# SkyRover.net
KiCad netlist of a schematic drawn in Altium Designer
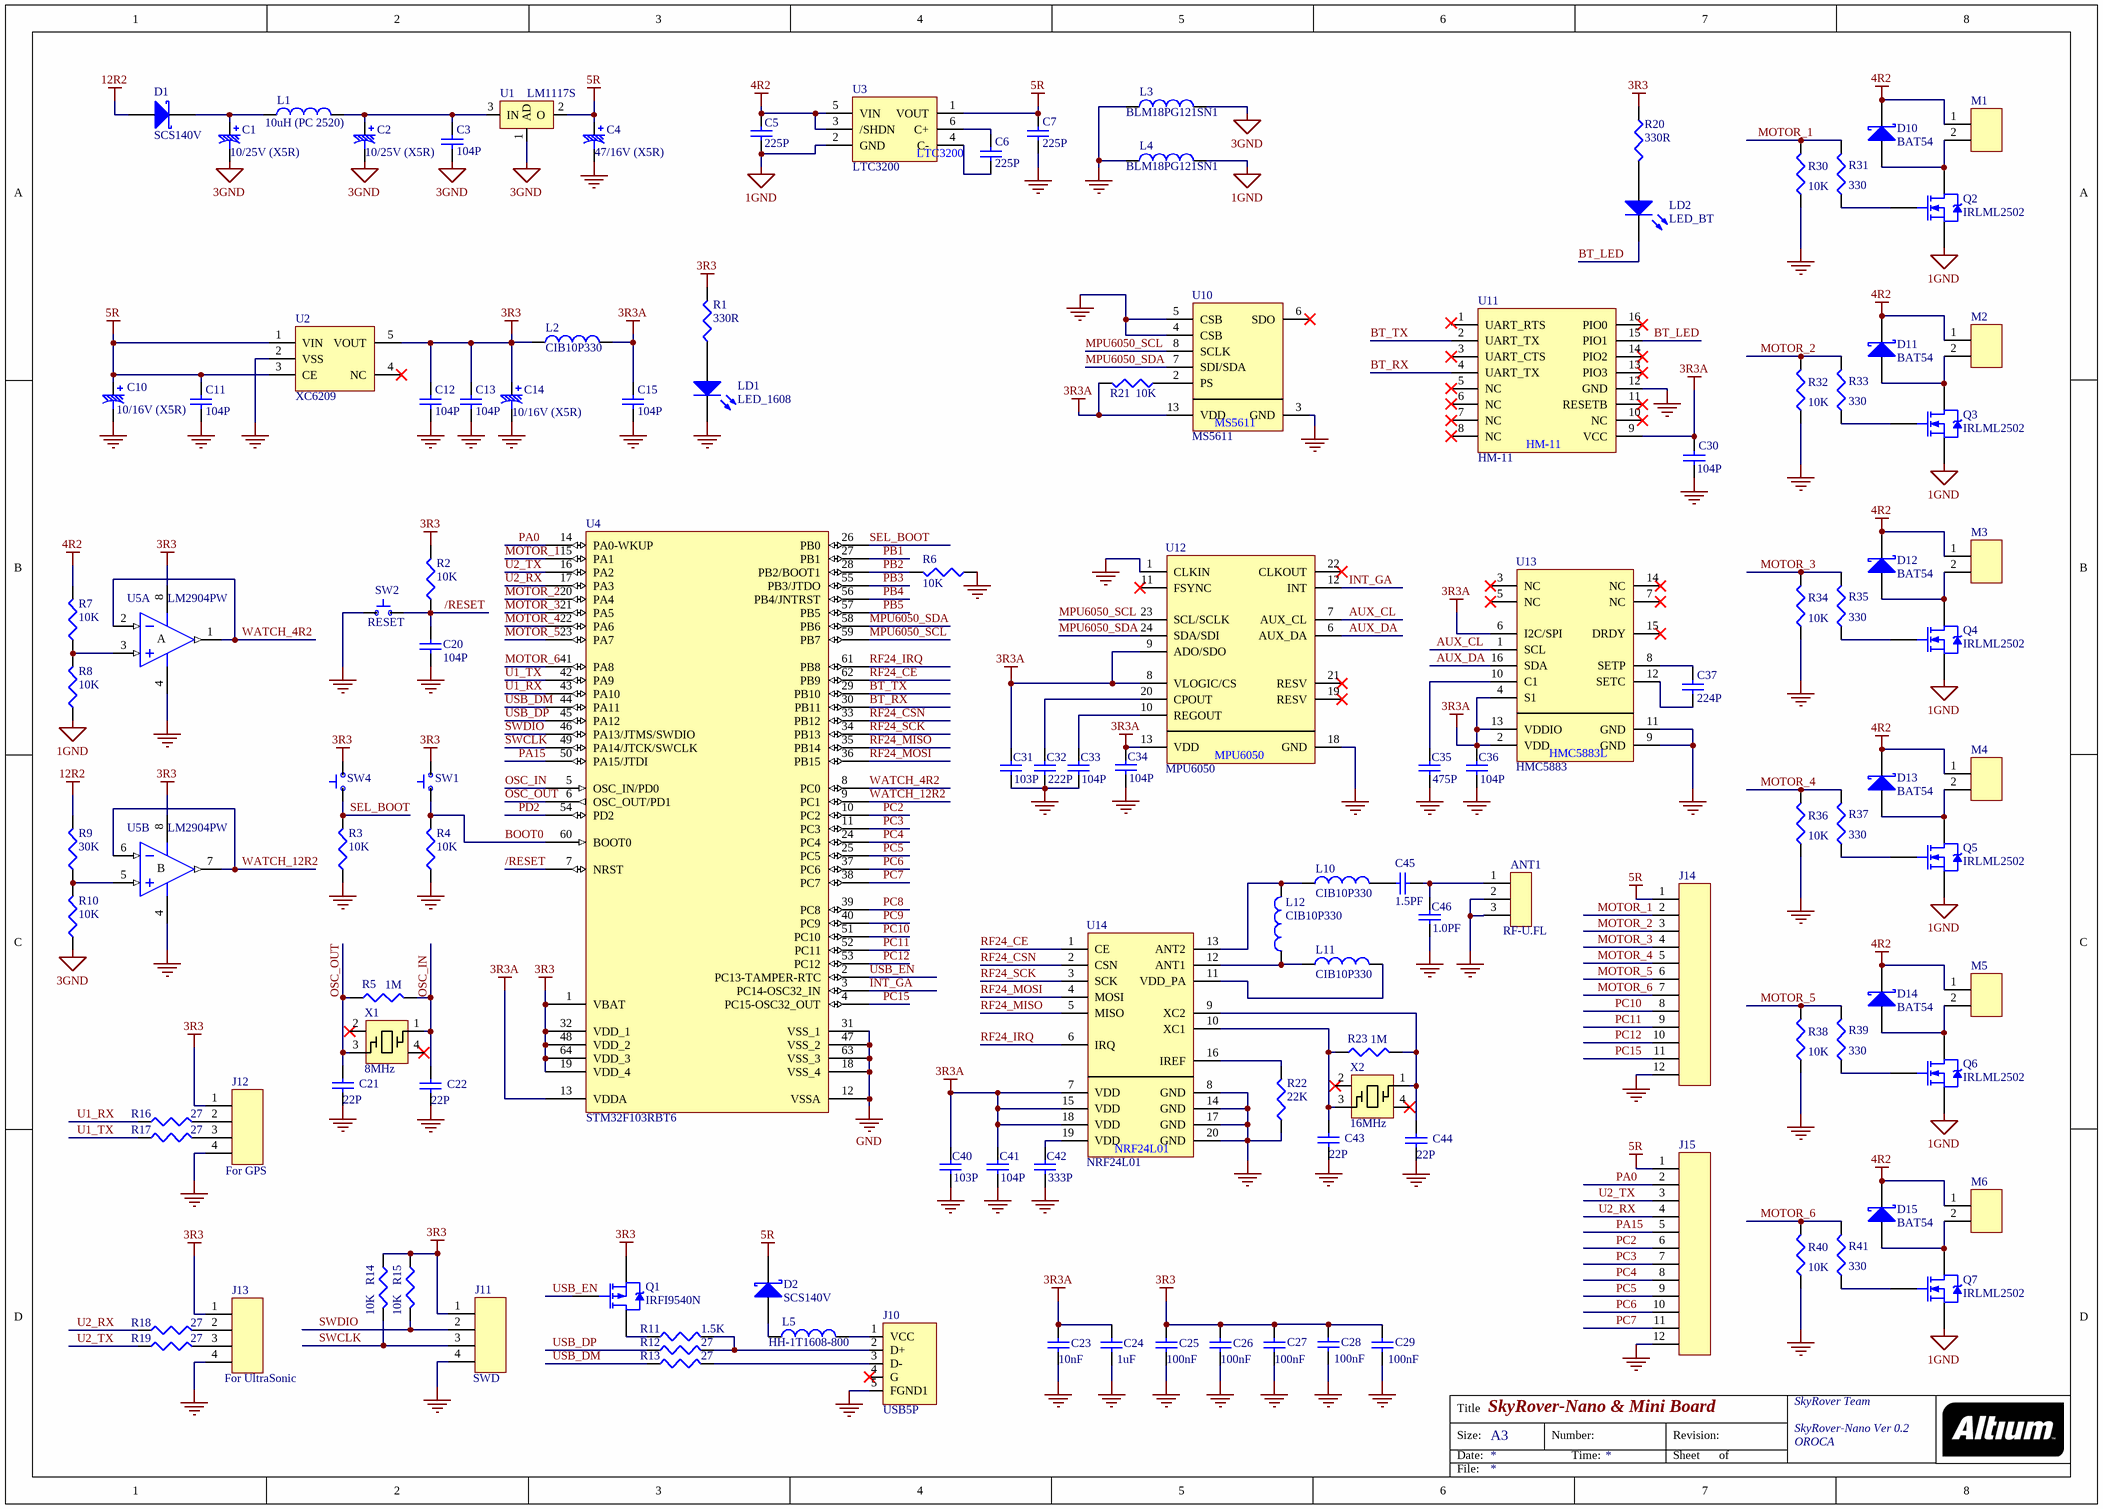
[diagram p0: SkyRover.SchDoc]

(export (version "E")
  (design (tool "Eeschema 10.0.6"))
  (components
    (comp (ref "ANT1") (value "RF-U.FL") (footprint "U.FL-R-SMT") (libsource (lib "KDG1") (part "RF-U.FL")))
    (comp (ref "C1")
      (value "10/25V (X5R)")
      (footprint "C_3.2X1.6")
      (description "Electrolytic Capacitor")
      (libsource (lib "烹钦扼捞宏矾府") (part "CAP_ELEC"))
    )
    (comp (ref "C2")
      (value "10/25V (X5R)")
      (footprint "C_3.2X1.6")
      (description "Electrolytic Capacitor")
      (libsource (lib "烹钦扼捞宏矾府") (part "CAP_ELEC"))
    )
    (comp (ref "C3")
      (value "104P")
      (footprint "C_1608(0603)")
      (description "Ceramic Capacitor")
      (libsource (lib "烹钦扼捞宏矾府") (part "CAP"))
    )
    (comp (ref "C4")
      (value "47/16V (X5R)")
      (footprint "C_3.2X1.6")
      (description "Electrolytic Capacitor")
      (libsource (lib "烹钦扼捞宏矾府") (part "CAP_ELEC"))
    )
    (comp (ref "C5")
      (value "225P")
      (footprint "C_1608(0603)")
      (description "Ceramic Capacitor")
      (libsource (lib "烹钦扼捞宏矾府") (part "CAP"))
    )
    (comp (ref "C6")
      (value "225P")
      (footprint "C_1608(0603)")
      (description "Ceramic Capacitor")
      (libsource (lib "烹钦扼捞宏矾府") (part "CAP"))
    )
    (comp (ref "C7")
      (value "225P")
      (footprint "C_1608(0603)")
      (description "Ceramic Capacitor")
      (libsource (lib "烹钦扼捞宏矾府") (part "CAP"))
    )
    (comp (ref "C10")
      (value "10/16V (X5R)")
      (footprint "C_3.2X1.6")
      (description "Electrolytic Capacitor")
      (libsource (lib "烹钦扼捞宏矾府") (part "CAP_ELEC"))
    )
    (comp (ref "C11")
      (value "104P")
      (footprint "C_1608(0603)")
      (description "Ceramic Capacitor")
      (libsource (lib "烹钦扼捞宏矾府") (part "CAP"))
    )
    (comp (ref "C12")
      (value "104P")
      (footprint "C_1608(0603)")
      (description "Ceramic Capacitor")
      (libsource (lib "烹钦扼捞宏矾府") (part "CAP"))
    )
    (comp (ref "C13")
      (value "104P")
      (footprint "C_1608(0603)")
      (description "Ceramic Capacitor")
      (libsource (lib "烹钦扼捞宏矾府") (part "CAP"))
    )
    (comp (ref "C14")
      (value "10/16V (X5R)")
      (footprint "C_3.2X1.6")
      (description "Electrolytic Capacitor")
      (libsource (lib "烹钦扼捞宏矾府") (part "CAP_ELEC"))
    )
    (comp (ref "C15")
      (value "104P")
      (footprint "C_1608(0603)")
      (description "Ceramic Capacitor")
      (libsource (lib "烹钦扼捞宏矾府") (part "CAP"))
    )
    (comp (ref "C20")
      (value "104P")
      (footprint "C_2012(0805)")
      (description "Ceramic Capacitor")
      (libsource (lib "烹钦扼捞宏矾府") (part "CAP"))
    )
    (comp (ref "C21")
      (value "22P")
      (footprint "C_1608(0603)")
      (description "Ceramic Capacitor")
      (libsource (lib "烹钦扼捞宏矾府") (part "CAP"))
    )
    (comp (ref "C22")
      (value "22P")
      (footprint "C_1608(0603)")
      (description "Ceramic Capacitor")
      (libsource (lib "烹钦扼捞宏矾府") (part "CAP"))
    )
    (comp (ref "C23")
      (value "10nF")
      (footprint "C_1608(0603)")
      (description "Ceramic Capacitor")
      (libsource (lib "烹钦扼捞宏矾府") (part "CAP"))
    )
    (comp (ref "C24")
      (value "1uF")
      (footprint "C_2012(0805)")
      (description "Ceramic Capacitor")
      (libsource (lib "烹钦扼捞宏矾府") (part "CAP"))
    )
    (comp (ref "C25")
      (value "100nF")
      (footprint "C_1608(0603)")
      (description "Ceramic Capacitor")
      (libsource (lib "烹钦扼捞宏矾府") (part "CAP"))
    )
    (comp (ref "C26")
      (value "100nF")
      (footprint "C_1608(0603)")
      (description "Ceramic Capacitor")
      (libsource (lib "烹钦扼捞宏矾府") (part "CAP"))
    )
    (comp (ref "C27")
      (value "100nF")
      (footprint "C_1608(0603)")
      (description "Ceramic Capacitor")
      (libsource (lib "烹钦扼捞宏矾府") (part "CAP"))
    )
    (comp (ref "C28")
      (value "100nF")
      (footprint "C_1608(0603)")
      (description "Ceramic Capacitor")
      (libsource (lib "烹钦扼捞宏矾府") (part "CAP"))
    )
    (comp (ref "C29")
      (value "100nF")
      (footprint "C_1608(0603)")
      (description "Ceramic Capacitor")
      (libsource (lib "烹钦扼捞宏矾府") (part "CAP"))
    )
    (comp (ref "C30")
      (value "104P")
      (footprint "C_1608(0603)")
      (description "Ceramic Capacitor")
      (libsource (lib "烹钦扼捞宏矾府") (part "CAP"))
    )
    (comp (ref "C31")
      (value "103P")
      (footprint "C_1608(0603)")
      (description "Ceramic Capacitor")
      (libsource (lib "烹钦扼捞宏矾府") (part "CAP"))
    )
    (comp (ref "C32")
      (value "222P")
      (footprint "C_1608(0603)")
      (description "Ceramic Capacitor")
      (libsource (lib "烹钦扼捞宏矾府") (part "CAP"))
    )
    (comp (ref "C33")
      (value "104P")
      (footprint "C_1608(0603)")
      (description "Ceramic Capacitor")
      (libsource (lib "烹钦扼捞宏矾府") (part "CAP"))
    )
    (comp (ref "C34")
      (value "104P")
      (footprint "C_1608(0603)")
      (description "Ceramic Capacitor")
      (libsource (lib "烹钦扼捞宏矾府") (part "CAP"))
    )
    (comp (ref "C35")
      (value "475P")
      (footprint "C_1608(0603)")
      (description "Ceramic Capacitor")
      (libsource (lib "烹钦扼捞宏矾府") (part "CAP"))
    )
    (comp (ref "C36")
      (value "104P")
      (footprint "C_1608(0603)")
      (description "Ceramic Capacitor")
      (libsource (lib "烹钦扼捞宏矾府") (part "CAP"))
    )
    (comp (ref "C37")
      (value "224P")
      (footprint "C_1608(0603)")
      (description "Ceramic Capacitor")
      (libsource (lib "烹钦扼捞宏矾府") (part "CAP"))
    )
    (comp (ref "C40")
      (value "103P")
      (footprint "C_1608(0603)")
      (description "Ceramic Capacitor")
      (libsource (lib "烹钦扼捞宏矾府") (part "CAP"))
    )
    (comp (ref "C41")
      (value "104P")
      (footprint "C_1608(0603)")
      (description "Ceramic Capacitor")
      (libsource (lib "烹钦扼捞宏矾府") (part "CAP"))
    )
    (comp (ref "C42")
      (value "333P")
      (footprint "C_1608(0603)")
      (description "Ceramic Capacitor")
      (libsource (lib "烹钦扼捞宏矾府") (part "CAP"))
    )
    (comp (ref "C43")
      (value "22P")
      (footprint "C_1608(0603)")
      (description "Ceramic Capacitor")
      (libsource (lib "烹钦扼捞宏矾府") (part "CAP"))
    )
    (comp (ref "C44")
      (value "22P")
      (footprint "C_1608(0603)")
      (description "Ceramic Capacitor")
      (libsource (lib "烹钦扼捞宏矾府") (part "CAP"))
    )
    (comp (ref "C45")
      (value "1.5PF")
      (footprint "C_1608(0603)")
      (description "Ceramic Capacitor")
      (libsource (lib "烹钦扼捞宏矾府") (part "CAP"))
    )
    (comp (ref "C46")
      (value "1.0PF")
      (footprint "C_1608(0603)")
      (description "Ceramic Capacitor")
      (libsource (lib "烹钦扼捞宏矾府") (part "CAP"))
    )
    (comp (ref "D1")
      (value "SCS140V")
      (footprint "SMB")
      (description "Schottky Diode")
      (fields (field (name "PUBLISHER") "Altium Limited"))
      (libsource (lib "Miscellaneous Devices") (part "D Schottky"))
    )
    (comp (ref "D2")
      (value "SCS140V")
      (footprint "SMB")
      (description "Schottky Diode")
      (fields (field (name "PUBLISHER") "Altium Limited"))
      (libsource (lib "Miscellaneous Devices") (part "D Schottky"))
    )
    (comp (ref "D10")
      (value "BAT54")
      (footprint "SOT23_N")
      (description "Schottky Barrier Diode")
      (fields (field (name "PUBLISHER") "Altium Limited"))
      (libsource (lib "Philips Discrete Diode - Schottky") (part "BAT54"))
    )
    (comp (ref "D11")
      (value "BAT54")
      (footprint "SOT23_N")
      (description "Schottky Barrier Diode")
      (fields (field (name "PUBLISHER") "Altium Limited"))
      (libsource (lib "Philips Discrete Diode - Schottky") (part "BAT54"))
    )
    (comp (ref "D12")
      (value "BAT54")
      (footprint "SOT23_N")
      (description "Schottky Barrier Diode")
      (fields (field (name "PUBLISHER") "Altium Limited"))
      (libsource (lib "Philips Discrete Diode - Schottky") (part "BAT54"))
    )
    (comp (ref "D13")
      (value "BAT54")
      (footprint "SOT23_N")
      (description "Schottky Barrier Diode")
      (fields (field (name "PUBLISHER") "Altium Limited"))
      (libsource (lib "Philips Discrete Diode - Schottky") (part "BAT54"))
    )
    (comp (ref "D14")
      (value "BAT54")
      (footprint "SOT23_N")
      (description "Schottky Barrier Diode")
      (fields (field (name "PUBLISHER") "Altium Limited"))
      (libsource (lib "Philips Discrete Diode - Schottky") (part "BAT54"))
    )
    (comp (ref "D15")
      (value "BAT54")
      (footprint "SOT23_N")
      (description "Schottky Barrier Diode")
      (fields (field (name "PUBLISHER") "Altium Limited"))
      (libsource (lib "Philips Discrete Diode - Schottky") (part "BAT54"))
    )
    (comp (ref "J10")
      (value "USB5P")
      (footprint "USB-MIN5P")
      (description "Connector USB")
      (libsource (lib "VR-SW-JACK") (part "USB5P"))
    )
    (comp (ref "J11")
      (value "SWD")
      (footprint "MOLEX-53398-0471")
      (libsource (lib "KDG1") (part "MOLEX-53398-471"))
    )
    (comp (ref "J12")
      (value "For GPS")
      (footprint "MOLEX-53398-0471")
      (libsource (lib "KDG1") (part "MOLEX-53398-471"))
    )
    (comp (ref "J13")
      (value "For UltraSonic")
      (footprint "MOLEX-53398-0471")
      (libsource (lib "KDG1") (part "MOLEX-53398-471"))
    )
    (comp (ref "J14")
      (value "MOLEX-53398-1271")
      (footprint "MOLEX-53398-1271")
      (libsource (lib "KDG1") (part "MOLEX-53398-1271"))
    )
    (comp (ref "J15")
      (value "MOLEX-53398-1271")
      (footprint "MOLEX-53398-1271")
      (libsource (lib "KDG1") (part "MOLEX-53398-1271"))
    )
    (comp (ref "L1")
      (value "10uH (PC 2520)")
      (footprint "INDC1608L")
      (description "Inductor")
      (fields (field (name "PUBLISHER") "Altium Limited"))
      (libsource (lib "Miscellaneous Devices") (part "Inductor"))
    )
    (comp (ref "L2")
      (value "CIB10P330")
      (footprint "INDC1608L")
      (description "Inductor")
      (fields (field (name "PUBLISHER") "Altium Limited"))
      (libsource (lib "Miscellaneous Devices") (part "Inductor"))
    )
    (comp (ref "L3")
      (value "BLM18PG121SN1")
      (footprint "INDC1608L")
      (description "Inductor")
      (fields (field (name "PUBLISHER") "Altium Limited"))
      (libsource (lib "Miscellaneous Devices") (part "Inductor"))
    )
    (comp (ref "L4")
      (value "BLM18PG121SN1")
      (footprint "INDC1608L")
      (description "Inductor")
      (fields (field (name "PUBLISHER") "Altium Limited"))
      (libsource (lib "Miscellaneous Devices") (part "Inductor"))
    )
    (comp (ref "L5")
      (value "HH-1T1608-800")
      (footprint "INDC1608L")
      (description "Inductor")
      (fields (field (name "PUBLISHER") "Altium Limited"))
      (libsource (lib "Miscellaneous Devices") (part "Inductor"))
    )
    (comp (ref "L10")
      (value "CIB10P330")
      (footprint "INDC1608L")
      (description "Inductor")
      (fields (field (name "PUBLISHER") "Altium Limited"))
      (libsource (lib "Miscellaneous Devices") (part "Inductor"))
    )
    (comp (ref "L11")
      (value "CIB10P330")
      (footprint "INDC1608L")
      (description "Inductor")
      (fields (field (name "PUBLISHER") "Altium Limited"))
      (libsource (lib "Miscellaneous Devices") (part "Inductor"))
    )
    (comp (ref "L12")
      (value "CIB10P330")
      (footprint "INDC1608L")
      (description "Inductor")
      (fields (field (name "PUBLISHER") "Altium Limited"))
      (libsource (lib "Miscellaneous Devices") (part "Inductor"))
    )
    (comp (ref "LD1")
      (value "LED_1608")
      (footprint "LED_1608(0603)")
      (description "IBLUE")
      (libsource (lib "烹钦扼捞宏矾府") (part "LED"))
    )
    (comp (ref "LD2")
      (value "LED_BT")
      (footprint "LED_1608(0603)")
      (description "IBLUE")
      (libsource (lib "烹钦扼捞宏矾府") (part "LED"))
    )
    (comp (ref "M1")
      (value "MOLEX53261-0271")
      (footprint "KDG1:MOLEX-53261-0271")
      (libsource (lib "KDG1") (part "MOLEX53261-0271"))
    )
    (comp (ref "M2")
      (value "MOLEX53261-0271")
      (footprint "KDG1:MOLEX-53261-0271")
      (libsource (lib "KDG1") (part "MOLEX53261-0271"))
    )
    (comp (ref "M3")
      (value "MOLEX53261-0271")
      (footprint "KDG1:MOLEX-53261-0271")
      (libsource (lib "KDG1") (part "MOLEX53261-0271"))
    )
    (comp (ref "M4")
      (value "MOLEX53261-0271")
      (footprint "KDG1:MOLEX-53261-0271")
      (libsource (lib "KDG1") (part "MOLEX53261-0271"))
    )
    (comp (ref "M5")
      (value "MOLEX53261-0271")
      (footprint "KDG1:MOLEX-53261-0271")
      (libsource (lib "KDG1") (part "MOLEX53261-0271"))
    )
    (comp (ref "M6")
      (value "MOLEX53261-0271")
      (footprint "KDG1:MOLEX-53261-0271")
      (libsource (lib "KDG1") (part "MOLEX53261-0271"))
    )
    (comp (ref "Q1")
      (value "IRFI9540N")
      (footprint "TO-220_FullPak")
      (description "HEXFET Power MOSFET")
      (fields (field (name "PUBLISHER") "Altium Limited"))
      (libsource (lib "IR Discrete MOSFET - Power") (part "IRFI9540N"))
    )
    (comp (ref "Q2")
      (value "IRLML2502")
      (footprint "SOT-23_N")
      (description "HEXFET Power MOSFET")
      (fields (field (name "PUBLISHER") "Altium Limited"))
      (libsource (lib "IR Discrete MOSFET - Power") (part "IRLML2402"))
    )
    (comp (ref "Q3")
      (value "IRLML2502")
      (footprint "SOT-23_N")
      (description "HEXFET Power MOSFET")
      (fields (field (name "PUBLISHER") "Altium Limited"))
      (libsource (lib "IR Discrete MOSFET - Power") (part "IRLML2402"))
    )
    (comp (ref "Q4")
      (value "IRLML2502")
      (footprint "SOT-23_N")
      (description "HEXFET Power MOSFET")
      (fields (field (name "PUBLISHER") "Altium Limited"))
      (libsource (lib "IR Discrete MOSFET - Power") (part "IRLML2402"))
    )
    (comp (ref "Q5")
      (value "IRLML2502")
      (footprint "SOT-23_N")
      (description "HEXFET Power MOSFET")
      (fields (field (name "PUBLISHER") "Altium Limited"))
      (libsource (lib "IR Discrete MOSFET - Power") (part "IRLML2402"))
    )
    (comp (ref "Q6")
      (value "IRLML2502")
      (footprint "SOT-23_N")
      (description "HEXFET Power MOSFET")
      (fields (field (name "PUBLISHER") "Altium Limited"))
      (libsource (lib "IR Discrete MOSFET - Power") (part "IRLML2402"))
    )
    (comp (ref "Q7")
      (value "IRLML2502")
      (footprint "SOT-23_N")
      (description "HEXFET Power MOSFET")
      (fields (field (name "PUBLISHER") "Altium Limited"))
      (libsource (lib "IR Discrete MOSFET - Power") (part "IRLML2402"))
    )
    (comp (ref "R1")
      (value "330R")
      (footprint "R_1608(0603)")
      (description "Chip Resistor")
      (libsource (lib "烹钦扼捞宏矾府") (part "RES1"))
    )
    (comp (ref "R2")
      (value "10K")
      (footprint "R_1608(0603)")
      (description "Chip Resistor")
      (libsource (lib "烹钦扼捞宏矾府") (part "RES1"))
    )
    (comp (ref "R3")
      (value "10K")
      (footprint "R_1608(0603)")
      (description "Chip Resistor")
      (libsource (lib "烹钦扼捞宏矾府") (part "RES1"))
    )
    (comp (ref "R4")
      (value "10K")
      (footprint "R_1608(0603)")
      (description "Chip Resistor")
      (libsource (lib "烹钦扼捞宏矾府") (part "RES1"))
    )
    (comp (ref "R5")
      (value "1M")
      (footprint "J1-0603")
      (description "Resistor")
      (fields (field (name "PUBLISHER") "Altium Limited"))
      (libsource (lib "Miscellaneous Devices") (part "Res3"))
    )
    (comp (ref "R6")
      (value "10K")
      (footprint "R_1608(0603)")
      (description "Chip Resistor")
      (libsource (lib "烹钦扼捞宏矾府") (part "RES1"))
    )
    (comp (ref "R7")
      (value "10K")
      (footprint "R_1608(0603)")
      (description "Chip Resistor")
      (libsource (lib "烹钦扼捞宏矾府") (part "RES1"))
    )
    (comp (ref "R8")
      (value "10K")
      (footprint "R_1608(0603)")
      (description "Chip Resistor")
      (libsource (lib "烹钦扼捞宏矾府") (part "RES1"))
    )
    (comp (ref "R9")
      (value "30K")
      (footprint "R_1608(0603)")
      (description "Chip Resistor")
      (libsource (lib "烹钦扼捞宏矾府") (part "RES1"))
    )
    (comp (ref "R10")
      (value "10K")
      (footprint "R_1608(0603)")
      (description "Chip Resistor")
      (libsource (lib "烹钦扼捞宏矾府") (part "RES1"))
    )
    (comp (ref "R11")
      (value "1.5K")
      (footprint "J1-0603")
      (description "Resistor")
      (fields (field (name "PUBLISHER") "Altium Limited"))
      (libsource (lib "Miscellaneous Devices") (part "Res3"))
    )
    (comp (ref "R12")
      (value "27")
      (footprint "J1-0603")
      (description "Resistor")
      (fields (field (name "PUBLISHER") "Altium Limited"))
      (libsource (lib "Miscellaneous Devices") (part "Res3"))
    )
    (comp (ref "R13")
      (value "27")
      (footprint "J1-0603")
      (description "Resistor")
      (fields (field (name "PUBLISHER") "Altium Limited"))
      (libsource (lib "Miscellaneous Devices") (part "Res3"))
    )
    (comp (ref "R14")
      (value "10K")
      (footprint "J1-0603")
      (description "Resistor")
      (fields (field (name "PUBLISHER") "Altium Limited"))
      (libsource (lib "Miscellaneous Devices") (part "Res3"))
    )
    (comp (ref "R15")
      (value "10K")
      (footprint "J1-0603")
      (description "Resistor")
      (fields (field (name "PUBLISHER") "Altium Limited"))
      (libsource (lib "Miscellaneous Devices") (part "Res3"))
    )
    (comp (ref "R16")
      (value "27")
      (footprint "J1-0603")
      (description "Resistor")
      (fields (field (name "PUBLISHER") "Altium Limited"))
      (libsource (lib "Miscellaneous Devices") (part "Res3"))
    )
    (comp (ref "R17")
      (value "27")
      (footprint "J1-0603")
      (description "Resistor")
      (fields (field (name "PUBLISHER") "Altium Limited"))
      (libsource (lib "Miscellaneous Devices") (part "Res3"))
    )
    (comp (ref "R18")
      (value "27")
      (footprint "J1-0603")
      (description "Resistor")
      (fields (field (name "PUBLISHER") "Altium Limited"))
      (libsource (lib "Miscellaneous Devices") (part "Res3"))
    )
    (comp (ref "R19")
      (value "27")
      (footprint "J1-0603")
      (description "Resistor")
      (fields (field (name "PUBLISHER") "Altium Limited"))
      (libsource (lib "Miscellaneous Devices") (part "Res3"))
    )
    (comp (ref "R20")
      (value "330R")
      (footprint "R_1608(0603)")
      (description "Chip Resistor")
      (libsource (lib "烹钦扼捞宏矾府") (part "RES1"))
    )
    (comp (ref "R21")
      (value "10K")
      (footprint "R_1608(0603)")
      (description "Chip Resistor")
      (libsource (lib "烹钦扼捞宏矾府") (part "RES1"))
    )
    (comp (ref "R22")
      (value "22K")
      (footprint "R_1608(0603)")
      (description "Chip Resistor")
      (libsource (lib "烹钦扼捞宏矾府") (part "RES1"))
    )
    (comp (ref "R23")
      (value "1M")
      (footprint "J1-0603")
      (description "Resistor")
      (fields (field (name "PUBLISHER") "Altium Limited"))
      (libsource (lib "Miscellaneous Devices") (part "Res3"))
    )
    (comp (ref "R30")
      (value "10K")
      (footprint "R_1608(0603)")
      (description "Chip Resistor")
      (libsource (lib "烹钦扼捞宏矾府") (part "RES1"))
    )
    (comp (ref "R31")
      (value "330")
      (footprint "J1-0603")
      (description "Resistor")
      (fields (field (name "PUBLISHER") "Altium Limited"))
      (libsource (lib "Miscellaneous Devices") (part "Res3"))
    )
    (comp (ref "R32")
      (value "10K")
      (footprint "R_1608(0603)")
      (description "Chip Resistor")
      (libsource (lib "烹钦扼捞宏矾府") (part "RES1"))
    )
    (comp (ref "R33")
      (value "330")
      (footprint "J1-0603")
      (description "Resistor")
      (fields (field (name "PUBLISHER") "Altium Limited"))
      (libsource (lib "Miscellaneous Devices") (part "Res3"))
    )
    (comp (ref "R34")
      (value "10K")
      (footprint "R_1608(0603)")
      (description "Chip Resistor")
      (libsource (lib "烹钦扼捞宏矾府") (part "RES1"))
    )
    (comp (ref "R35")
      (value "330")
      (footprint "J1-0603")
      (description "Resistor")
      (fields (field (name "PUBLISHER") "Altium Limited"))
      (libsource (lib "Miscellaneous Devices") (part "Res3"))
    )
    (comp (ref "R36")
      (value "10K")
      (footprint "R_1608(0603)")
      (description "Chip Resistor")
      (libsource (lib "烹钦扼捞宏矾府") (part "RES1"))
    )
    (comp (ref "R37")
      (value "330")
      (footprint "J1-0603")
      (description "Resistor")
      (fields (field (name "PUBLISHER") "Altium Limited"))
      (libsource (lib "Miscellaneous Devices") (part "Res3"))
    )
    (comp (ref "R38")
      (value "10K")
      (footprint "R_1608(0603)")
      (description "Chip Resistor")
      (libsource (lib "烹钦扼捞宏矾府") (part "RES1"))
    )
    (comp (ref "R39")
      (value "330")
      (footprint "J1-0603")
      (description "Resistor")
      (fields (field (name "PUBLISHER") "Altium Limited"))
      (libsource (lib "Miscellaneous Devices") (part "Res3"))
    )
    (comp (ref "R40")
      (value "10K")
      (footprint "R_1608(0603)")
      (description "Chip Resistor")
      (libsource (lib "烹钦扼捞宏矾府") (part "RES1"))
    )
    (comp (ref "R41")
      (value "330")
      (footprint "J1-0603")
      (description "Resistor")
      (fields (field (name "PUBLISHER") "Altium Limited"))
      (libsource (lib "Miscellaneous Devices") (part "Res3"))
    )
    (comp (ref "SW1")
      (value "~")
      (footprint "CTT-1101NEA-160")
      (description "SMD push switch")
      (libsource (lib "") (part "SWITCH_1"))
    )
    (comp (ref "SW2")
      (value "RESET")
      (footprint "CTT-1101NEA-160")
      (description "SMD push switch")
      (libsource (lib "烹钦扼捞宏矾府") (part "SWITCH"))
    )
    (comp (ref "SW4")
      (value "~")
      (footprint "CTT-1101NEA-160")
      (description "SMD push switch")
      (libsource (lib "") (part "SWITCH_1"))
    )
    (comp (ref "U1")
      (value "LM1117S")
      (footprint "SOT223")
      (description "IC")
      (libsource (lib "CHIP") (part "LM1117S"))
    )
    (comp (ref "U2") (value "XC6209") (footprint "XC6209") (libsource (lib "KDG1") (part "XC6209")))
    (comp (ref "U3") (value "LTC3200") (footprint "LTC3200") (libsource (lib "KDG1") (part "LTC3200")))
    (comp (ref "U4")
      (value "STM32F103RBT6")
      (footprint "LQFP64_M")
      (description "STM32 ARM-based 32-bit MCU with 128 Kbytes Flash, 64-pin LQFP, Industrial Temperature")
      (fields (field (name "PUBLISHER") "Altium Limited"))
      (libsource (lib "ST Microcontroller 32-Bit STM32") (part "STM32F103RBT6"))
    )
    (comp (ref "U5")
      (value "LM2904PW")
      (footprint "PW008_M")
      (description "Dual Operational Amplifier")
      (fields (field (name "PUBLISHER") "Altium Limited"))
      (libsource (lib "TI Operational Amplifier") (part "LM2904PW"))
    )
    (comp (ref "U10") (value "MS5611") (footprint "MS5611") (libsource (lib "KDG1") (part "MS5611")))
    (comp (ref "U11") (value "HM-11") (footprint "HM-11") (libsource (lib "KDG1") (part "HM-11")))
    (comp (ref "U12") (value "MPU6050") (footprint "MPU6050") (libsource (lib "KDG1") (part "MPU6050")))
    (comp (ref "U13") (value "HMC5883") (footprint "HMC5883L") (libsource (lib "KDG1") (part "HMC5883")))
    (comp (ref "U14")
      (value "NRF24L01")
      (footprint "KDG1:nRF24L01")
      (libsource (lib "KDG1") (part "NRF24L01"))
    )
    (comp (ref "X1") (value "8MHz") (footprint "OSC_5032") (libsource (lib "KDG1") (part "OSC_5032")))
    (comp (ref "X2") (value "16MHz") (footprint "OSC_5032") (libsource (lib "KDG1") (part "OSC_5032")))
  )
  (nets
    (net (code "1") (name "/AUX_CL") (class "Default")
      (node (ref "U12") (pin "7") (pinfunction "AUX_CL_7") (pintype "passive"))
      (node (ref "U13") (pin "1") (pinfunction "SCL_1") (pintype "passive"))
    )
    (net (code "2") (name "/AUX_DA") (class "Default")
      (node (ref "U12") (pin "6") (pinfunction "AUX_DA_6") (pintype "passive"))
      (node (ref "U13") (pin "16") (pinfunction "SDA_16") (pintype "passive"))
    )
    (net (code "3") (name "/BOOT0") (class "Default")
      (node (ref "R4") (pin "2") (pinfunction "2_2") (pintype "passive"))
      (node (ref "SW1") (pin "1") (pintype "passive"))
      (node (ref "U4") (pin "60") (pinfunction "BOOT0_60") (pintype "input"))
    )
    (net (code "4") (name "/BT_LED") (class "Default")
      (node (ref "LD2") (pin "2") (pinfunction "K_2") (pintype "passive"))
      (node (ref "U11") (pin "15") (pinfunction "PIO1_15") (pintype "passive"))
    )
    (net (code "5") (name "/BT_RX") (class "Default")
      (node (ref "U11") (pin "4") (pinfunction "UART_TX_4") (pintype "passive"))
      (node (ref "U4") (pin "30") (pinfunction "PB11_30") (pintype "bidirectional"))
    )
    (net (code "6") (name "/BT_TX") (class "Default")
      (node (ref "U11") (pin "2") (pinfunction "UART_TX_2") (pintype "passive"))
      (node (ref "U4") (pin "29") (pinfunction "PB10_29") (pintype "bidirectional"))
    )
    (net (code "7") (name "/INT_GA") (class "Default")
      (node (ref "U12") (pin "12") (pinfunction "INT_12") (pintype "passive"))
      (node (ref "U4") (pin "3") (pinfunction "PC14-OSC32_IN_3") (pintype "bidirectional"))
    )
    (net (code "8") (name "/MOTOR_1") (class "Default")
      (node (ref "J14") (pin "2") (pinfunction "2_2") (pintype "passive"))
      (node (ref "R30") (pin "2") (pinfunction "2_2") (pintype "passive"))
      (node (ref "R31") (pin "2") (pinfunction "2_2") (pintype "passive"))
      (node (ref "U4") (pin "15") (pinfunction "PA1_15") (pintype "bidirectional"))
    )
    (net (code "9") (name "/MOTOR_2") (class "Default")
      (node (ref "J14") (pin "3") (pinfunction "3_3") (pintype "passive"))
      (node (ref "R32") (pin "2") (pinfunction "2_2") (pintype "passive"))
      (node (ref "R33") (pin "2") (pinfunction "2_2") (pintype "passive"))
      (node (ref "U4") (pin "20") (pinfunction "PA4_20") (pintype "bidirectional"))
    )
    (net (code "10") (name "/MOTOR_3") (class "Default")
      (node (ref "J14") (pin "4") (pinfunction "4_4") (pintype "passive"))
      (node (ref "R34") (pin "2") (pinfunction "2_2") (pintype "passive"))
      (node (ref "R35") (pin "2") (pinfunction "2_2") (pintype "passive"))
      (node (ref "U4") (pin "21") (pinfunction "PA5_21") (pintype "bidirectional"))
    )
    (net (code "11") (name "/MOTOR_4") (class "Default")
      (node (ref "J14") (pin "5") (pinfunction "5_5") (pintype "passive"))
      (node (ref "R36") (pin "2") (pinfunction "2_2") (pintype "passive"))
      (node (ref "R37") (pin "2") (pinfunction "2_2") (pintype "passive"))
      (node (ref "U4") (pin "22") (pinfunction "PA6_22") (pintype "bidirectional"))
    )
    (net (code "12") (name "/MOTOR_5") (class "Default")
      (node (ref "J14") (pin "6") (pinfunction "6_6") (pintype "passive"))
      (node (ref "R38") (pin "2") (pinfunction "2_2") (pintype "passive"))
      (node (ref "R39") (pin "2") (pinfunction "2_2") (pintype "passive"))
      (node (ref "U4") (pin "23") (pinfunction "PA7_23") (pintype "bidirectional"))
    )
    (net (code "13") (name "/MOTOR_6") (class "Default")
      (node (ref "J14") (pin "7") (pinfunction "7_7") (pintype "passive"))
      (node (ref "R40") (pin "2") (pinfunction "2_2") (pintype "passive"))
      (node (ref "R41") (pin "2") (pinfunction "2_2") (pintype "passive"))
      (node (ref "U4") (pin "41") (pinfunction "PA8_41") (pintype "bidirectional"))
    )
    (net (code "14") (name "/MPU6050_SCL") (class "Default")
      (node (ref "U10") (pin "8") (pinfunction "SCLK_8") (pintype "passive"))
      (node (ref "U12") (pin "23") (pinfunction "SCL/SCLK_23") (pintype "passive"))
      (node (ref "U4") (pin "59") (pinfunction "PB7_59") (pintype "bidirectional"))
    )
    (net (code "15") (name "/MPU6050_SDA") (class "Default")
      (node (ref "U10") (pin "7") (pinfunction "SDI/SDA_7") (pintype "passive"))
      (node (ref "U12") (pin "24") (pinfunction "SDA/SDI_24") (pintype "passive"))
      (node (ref "U4") (pin "58") (pinfunction "PB6_58") (pintype "bidirectional"))
    )
    (net (code "16") (name "/OSC_IN") (class "Default")
      (node (ref "C22") (pin "2") (pinfunction "2_2") (pintype "passive"))
      (node (ref "R5") (pin "2") (pinfunction "2_2") (pintype "passive"))
      (node (ref "U4") (pin "5") (pinfunction "OSC_IN/PD0_5") (pintype "input"))
      (node (ref "X1") (pin "1") (pintype "passive"))
    )
    (net (code "17") (name "/OSC_OUT") (class "Default")
      (node (ref "C21") (pin "2") (pinfunction "2_2") (pintype "passive"))
      (node (ref "R5") (pin "1") (pinfunction "1_1") (pintype "passive"))
      (node (ref "U4") (pin "6") (pinfunction "OSC_OUT/PD1_6") (pintype "output"))
      (node (ref "X1") (pin "3") (pintype "passive"))
    )
    (net (code "18") (name "/PA0") (class "Default")
      (node (ref "J15") (pin "2") (pinfunction "2_2") (pintype "passive"))
      (node (ref "U4") (pin "14") (pinfunction "PA0-WKUP_14") (pintype "bidirectional"))
    )
    (net (code "19") (name "/PA15") (class "Default")
      (node (ref "J15") (pin "5") (pinfunction "5_5") (pintype "passive"))
      (node (ref "U4") (pin "50") (pinfunction "PA15/JTDI_50") (pintype "bidirectional"))
    )
    (net (code "20") (name "/PB1") (class "Default")
      (node (ref "U4") (pin "27") (pinfunction "PB1_27") (pintype "bidirectional"))
    )
    (net (code "21") (name "/PB2") (class "Default")
      (node (ref "R6") (pin "2") (pinfunction "2_2") (pintype "passive"))
      (node (ref "U4") (pin "28") (pinfunction "PB2/BOOT1_28") (pintype "bidirectional"))
    )
    (net (code "22") (name "/PB3") (class "Default")
      (node (ref "U4") (pin "55") (pinfunction "PB3/JTDO_55") (pintype "bidirectional"))
    )
    (net (code "23") (name "/PB4") (class "Default")
      (node (ref "U4") (pin "56") (pinfunction "PB4/JNTRST_56") (pintype "bidirectional"))
    )
    (net (code "24") (name "/PB5") (class "Default")
      (node (ref "U4") (pin "57") (pinfunction "PB5_57") (pintype "bidirectional"))
    )
    (net (code "25") (name "/PC2") (class "Default")
      (node (ref "J15") (pin "6") (pinfunction "6_6") (pintype "passive"))
      (node (ref "U4") (pin "10") (pinfunction "PC2_10") (pintype "bidirectional"))
    )
    (net (code "26") (name "/PC3") (class "Default")
      (node (ref "J15") (pin "7") (pinfunction "7_7") (pintype "passive"))
      (node (ref "U4") (pin "11") (pinfunction "PC3_11") (pintype "bidirectional"))
    )
    (net (code "27") (name "/PC4") (class "Default")
      (node (ref "J15") (pin "8") (pinfunction "8_8") (pintype "passive"))
      (node (ref "U4") (pin "24") (pinfunction "PC4_24") (pintype "bidirectional"))
    )
    (net (code "28") (name "/PC5") (class "Default")
      (node (ref "J15") (pin "9") (pinfunction "9_9") (pintype "passive"))
      (node (ref "U4") (pin "25") (pinfunction "PC5_25") (pintype "bidirectional"))
    )
    (net (code "29") (name "/PC6") (class "Default")
      (node (ref "J15") (pin "10") (pinfunction "10_10") (pintype "passive"))
      (node (ref "U4") (pin "37") (pinfunction "PC6_37") (pintype "bidirectional"))
    )
    (net (code "30") (name "/PC7") (class "Default")
      (node (ref "J15") (pin "11") (pinfunction "11_11") (pintype "passive"))
      (node (ref "U4") (pin "38") (pinfunction "PC7_38") (pintype "bidirectional"))
    )
    (net (code "31") (name "/PC8") (class "Default")
      (node (ref "U4") (pin "39") (pinfunction "PC8_39") (pintype "bidirectional"))
    )
    (net (code "32") (name "/PC9") (class "Default")
      (node (ref "U4") (pin "40") (pinfunction "PC9_40") (pintype "bidirectional"))
    )
    (net (code "33") (name "/PC10") (class "Default")
      (node (ref "J14") (pin "8") (pinfunction "8_8") (pintype "passive"))
      (node (ref "U4") (pin "51") (pinfunction "PC10_51") (pintype "bidirectional"))
    )
    (net (code "34") (name "/PC11") (class "Default")
      (node (ref "J14") (pin "9") (pinfunction "9_9") (pintype "passive"))
      (node (ref "U4") (pin "52") (pinfunction "PC11_52") (pintype "bidirectional"))
    )
    (net (code "35") (name "/PC12") (class "Default")
      (node (ref "J14") (pin "10") (pinfunction "10_10") (pintype "passive"))
      (node (ref "U4") (pin "53") (pinfunction "PC12_53") (pintype "bidirectional"))
    )
    (net (code "36") (name "/PC15") (class "Default")
      (node (ref "J14") (pin "11") (pinfunction "11_11") (pintype "passive"))
      (node (ref "U4") (pin "4") (pinfunction "PC15-OSC32_OUT_4") (pintype "bidirectional"))
    )
    (net (code "37") (name "/PD2") (class "Default")
      (node (ref "U4") (pin "54") (pinfunction "PD2_54") (pintype "bidirectional"))
    )
    (net (code "38") (name "/RF24_CE") (class "Default")
      (node (ref "U14") (pin "1") (pinfunction "CE_1") (pintype "passive"))
      (node (ref "U4") (pin "62") (pinfunction "PB9_62") (pintype "bidirectional"))
    )
    (net (code "39") (name "/RF24_CSN") (class "Default")
      (node (ref "U14") (pin "2") (pinfunction "CSN_2") (pintype "passive"))
      (node (ref "U4") (pin "33") (pinfunction "PB12_33") (pintype "bidirectional"))
    )
    (net (code "40") (name "/RF24_IRQ") (class "Default")
      (node (ref "U14") (pin "6") (pinfunction "IRQ_6") (pintype "passive"))
      (node (ref "U4") (pin "61") (pinfunction "PB8_61") (pintype "bidirectional"))
    )
    (net (code "41") (name "/RF24_MISO") (class "Default")
      (node (ref "U14") (pin "5") (pinfunction "MISO_5") (pintype "passive"))
      (node (ref "U4") (pin "35") (pinfunction "PB14_35") (pintype "bidirectional"))
    )
    (net (code "42") (name "/RF24_MOSI") (class "Default")
      (node (ref "U14") (pin "4") (pinfunction "MOSI_4") (pintype "passive"))
      (node (ref "U4") (pin "36") (pinfunction "PB15_36") (pintype "bidirectional"))
    )
    (net (code "43") (name "/RF24_SCK") (class "Default")
      (node (ref "U14") (pin "3") (pinfunction "SCK_3") (pintype "passive"))
      (node (ref "U4") (pin "34") (pinfunction "PB13_34") (pintype "bidirectional"))
    )
    (net (code "44") (name "/SEL_BOOT") (class "Default")
      (node (ref "R3") (pin "2") (pinfunction "2_2") (pintype "passive"))
      (node (ref "SW4") (pin "1") (pintype "passive"))
      (node (ref "U4") (pin "26") (pinfunction "PB0_26") (pintype "bidirectional"))
    )
    (net (code "45") (name "/SWCLK") (class "Default")
      (node (ref "J11") (pin "3") (pinfunction "3_3") (pintype "passive"))
      (node (ref "R14") (pin "2") (pinfunction "2_2") (pintype "passive"))
      (node (ref "U4") (pin "49") (pinfunction "PA14/JTCK/SWCLK_49") (pintype "bidirectional"))
    )
    (net (code "46") (name "/SWDIO") (class "Default")
      (node (ref "J11") (pin "2") (pinfunction "2_2") (pintype "passive"))
      (node (ref "R15") (pin "2") (pinfunction "2_2") (pintype "passive"))
      (node (ref "U4") (pin "46") (pinfunction "PA13/JTMS/SWDIO_46") (pintype "bidirectional"))
    )
    (net (code "47") (name "/U1_RX") (class "Default")
      (node (ref "R16") (pin "1") (pinfunction "1_1") (pintype "passive"))
      (node (ref "U4") (pin "43") (pinfunction "PA10_43") (pintype "bidirectional"))
    )
    (net (code "48") (name "/U1_TX") (class "Default")
      (node (ref "R17") (pin "1") (pinfunction "1_1") (pintype "passive"))
      (node (ref "U4") (pin "42") (pinfunction "PA9_42") (pintype "bidirectional"))
    )
    (net (code "49") (name "/U2_RX") (class "Default")
      (node (ref "J15") (pin "4") (pinfunction "4_4") (pintype "passive"))
      (node (ref "R18") (pin "1") (pinfunction "1_1") (pintype "passive"))
      (node (ref "U4") (pin "17") (pinfunction "PA3_17") (pintype "bidirectional"))
    )
    (net (code "50") (name "/U2_TX") (class "Default")
      (node (ref "J15") (pin "3") (pinfunction "3_3") (pintype "passive"))
      (node (ref "R19") (pin "1") (pinfunction "1_1") (pintype "passive"))
      (node (ref "U4") (pin "16") (pinfunction "PA2_16") (pintype "bidirectional"))
    )
    (net (code "51") (name "/USB_DM") (class "Default")
      (node (ref "R13") (pin "1") (pinfunction "1_1") (pintype "passive"))
      (node (ref "U4") (pin "44") (pinfunction "PA11_44") (pintype "bidirectional"))
    )
    (net (code "52") (name "/USB_DP") (class "Default")
      (node (ref "R12") (pin "1") (pinfunction "1_1") (pintype "passive"))
      (node (ref "U4") (pin "45") (pinfunction "PA12_45") (pintype "bidirectional"))
    )
    (net (code "53") (name "/USB_EN") (class "Default")
      (node (ref "Q1") (pin "1") (pinfunction "G_1") (pintype "passive"))
      (node (ref "U4") (pin "2") (pinfunction "PC13-TAMPER-RTC_2") (pintype "bidirectional"))
    )
    (net (code "54") (name "/WATCH_4R2") (class "Default")
      (node (ref "U4") (pin "8") (pinfunction "PC0_8") (pintype "bidirectional"))
      (node (ref "U5") (pin "1") (pinfunction "OUT_1") (pintype "output"))
      (node (ref "U5") (pin "2") (pinfunction "IN-_2") (pintype "input"))
    )
    (net (code "55") (name "/WATCH_12R2") (class "Default")
      (node (ref "U4") (pin "9") (pinfunction "PC1_9") (pintype "bidirectional"))
      (node (ref "U5") (pin "6") (pinfunction "IN-_6") (pintype "input"))
      (node (ref "U5") (pin "7") (pinfunction "OUT_7") (pintype "output"))
    )
    (net (code "56") (name "/{slash}RESET") (class "Default")
      (node (ref "C20") (pin "2") (pinfunction "2_2") (pintype "passive"))
      (node (ref "R2") (pin "1") (pinfunction "1_1") (pintype "passive"))
      (node (ref "SW2") (pin "2") (pintype "passive"))
      (node (ref "U4") (pin "7") (pinfunction "NRST_7") (pintype "bidirectional"))
    )
    (net (code "57") (name "1GND") (class "Default")
      (node (ref "C5") (pin "1") (pinfunction "1_1") (pintype "passive"))
      (node (ref "L4") (pin "2") (pinfunction "2_2") (pintype "passive"))
      (node (ref "Q2") (pin "2") (pinfunction "S_2") (pintype "passive"))
      (node (ref "Q3") (pin "2") (pinfunction "S_2") (pintype "passive"))
      (node (ref "Q4") (pin "2") (pinfunction "S_2") (pintype "passive"))
      (node (ref "Q5") (pin "2") (pinfunction "S_2") (pintype "passive"))
      (node (ref "Q6") (pin "2") (pinfunction "S_2") (pintype "passive"))
      (node (ref "Q7") (pin "2") (pinfunction "S_2") (pintype "passive"))
      (node (ref "R8") (pin "1") (pinfunction "1_1") (pintype "passive"))
      (node (ref "U3") (pin "2") (pinfunction "GND_2") (pintype "passive"))
    )
    (net (code "58") (name "3GND") (class "Default")
      (node (ref "C1") (pin "2") (pinfunction "2_2") (pintype "passive"))
      (node (ref "C2") (pin "2") (pinfunction "2_2") (pintype "passive"))
      (node (ref "C3") (pin "1") (pinfunction "1_1") (pintype "passive"))
      (node (ref "L3") (pin "2") (pinfunction "2_2") (pintype "passive"))
      (node (ref "R10") (pin "1") (pinfunction "1_1") (pintype "passive"))
      (node (ref "U1") (pin "1") (pinfunction "AD_1") (pintype "passive"))
    )
    (net (code "59") (name "3R3") (class "Default")
      (node (ref "C12") (pin "2") (pinfunction "2_2") (pintype "passive"))
      (node (ref "C13") (pin "2") (pinfunction "2_2") (pintype "passive"))
      (node (ref "C14") (pin "1") (pinfunction "1_1") (pintype "passive"))
      (node (ref "C25") (pin "2") (pinfunction "2_2") (pintype "passive"))
      (node (ref "C26") (pin "2") (pinfunction "2_2") (pintype "passive"))
      (node (ref "C27") (pin "2") (pinfunction "2_2") (pintype "passive"))
      (node (ref "C28") (pin "2") (pinfunction "2_2") (pintype "passive"))
      (node (ref "C29") (pin "2") (pinfunction "2_2") (pintype "passive"))
      (node (ref "J11") (pin "1") (pinfunction "1_1") (pintype "passive"))
      (node (ref "J12") (pin "1") (pinfunction "1_1") (pintype "passive"))
      (node (ref "J13") (pin "1") (pinfunction "1_1") (pintype "passive"))
      (node (ref "L2") (pin "1") (pinfunction "1_1") (pintype "passive"))
      (node (ref "Q1") (pin "3") (pinfunction "S_3") (pintype "passive"))
      (node (ref "R1") (pin "2") (pinfunction "2_2") (pintype "passive"))
      (node (ref "R14") (pin "1") (pinfunction "1_1") (pintype "passive"))
      (node (ref "R15") (pin "1") (pinfunction "1_1") (pintype "passive"))
      (node (ref "R2") (pin "2") (pinfunction "2_2") (pintype "passive"))
      (node (ref "R20") (pin "1") (pinfunction "1_1") (pintype "passive"))
      (node (ref "SW1") (pin "2") (pintype "passive"))
      (node (ref "SW4") (pin "2") (pintype "passive"))
      (node (ref "U2") (pin "5") (pinfunction "VOUT_5") (pintype "passive"))
      (node (ref "U4") (pin "1") (pinfunction "VBAT_1") (pintype "power_in"))
      (node (ref "U4") (pin "19") (pinfunction "VDD_4_19") (pintype "power_in"))
      (node (ref "U4") (pin "32") (pinfunction "VDD_1_32") (pintype "power_in"))
      (node (ref "U4") (pin "48") (pinfunction "VDD_2_48") (pintype "power_in"))
      (node (ref "U4") (pin "64") (pinfunction "VDD_3_64") (pintype "power_in"))
      (node (ref "U5") (pin "8") (pinfunction "V+_8") (pintype "power_in"))
    )
    (net (code "60") (name "3R3A") (class "Default")
      (node (ref "C15") (pin "2") (pinfunction "2_2") (pintype "passive"))
      (node (ref "C23") (pin "2") (pinfunction "2_2") (pintype "passive"))
      (node (ref "C24") (pin "2") (pinfunction "2_2") (pintype "passive"))
      (node (ref "C30") (pin "2") (pinfunction "2_2") (pintype "passive"))
      (node (ref "C31") (pin "2") (pinfunction "2_2") (pintype "passive"))
      (node (ref "C34") (pin "2") (pinfunction "2_2") (pintype "passive"))
      (node (ref "C40") (pin "2") (pinfunction "2_2") (pintype "passive"))
      (node (ref "C41") (pin "2") (pinfunction "2_2") (pintype "passive"))
      (node (ref "L2") (pin "2") (pinfunction "2_2") (pintype "passive"))
      (node (ref "R21") (pin "2") (pinfunction "2_2") (pintype "passive"))
      (node (ref "U10") (pin "13") (pinfunction "VDD_13") (pintype "passive"))
      (node (ref "U11") (pin "9") (pinfunction "VCC_9") (pintype "passive"))
      (node (ref "U12") (pin "13") (pinfunction "VDD_13") (pintype "passive"))
      (node (ref "U12") (pin "8") (pinfunction "VLOGIC/CS_8") (pintype "passive"))
      (node (ref "U12") (pin "9") (pinfunction "ADO/SDO_9") (pintype "passive"))
      (node (ref "U13") (pin "13") (pinfunction "VDDIO_13") (pintype "passive"))
      (node (ref "U13") (pin "2") (pinfunction "VDD_2") (pintype "passive"))
      (node (ref "U13") (pin "4") (pinfunction "S1_4") (pintype "passive"))
      (node (ref "U13") (pin "6") (pinfunction "I2C/SPI_6") (pintype "passive"))
      (node (ref "U14") (pin "15") (pinfunction "VDD_15") (pintype "passive"))
      (node (ref "U14") (pin "18") (pinfunction "VDD_18") (pintype "passive"))
      (node (ref "U14") (pin "7") (pinfunction "VDD_7") (pintype "passive"))
      (node (ref "U4") (pin "13") (pinfunction "VDDA_13") (pintype "power_in"))
    )
    (net (code "61") (name "4R2") (class "Default")
      (node (ref "C5") (pin "2") (pinfunction "2_2") (pintype "passive"))
      (node (ref "D10") (pin "3") (pinfunction "K_3") (pintype "passive"))
      (node (ref "D11") (pin "3") (pinfunction "K_3") (pintype "passive"))
      (node (ref "D12") (pin "3") (pinfunction "K_3") (pintype "passive"))
      (node (ref "D13") (pin "3") (pinfunction "K_3") (pintype "passive"))
      (node (ref "D14") (pin "3") (pinfunction "K_3") (pintype "passive"))
      (node (ref "D15") (pin "3") (pinfunction "K_3") (pintype "passive"))
      (node (ref "M1") (pin "1") (pinfunction "1_1") (pintype "passive"))
      (node (ref "M2") (pin "1") (pinfunction "1_1") (pintype "passive"))
      (node (ref "M3") (pin "1") (pinfunction "1_1") (pintype "passive"))
      (node (ref "M4") (pin "1") (pinfunction "1_1") (pintype "passive"))
      (node (ref "M5") (pin "1") (pinfunction "1_1") (pintype "passive"))
      (node (ref "M6") (pin "1") (pinfunction "1_1") (pintype "passive"))
      (node (ref "R7") (pin "2") (pinfunction "2_2") (pintype "passive"))
      (node (ref "U3") (pin "3") (pinfunction "/SHDN_3") (pintype "passive"))
      (node (ref "U3") (pin "5") (pinfunction "VIN_5") (pintype "passive"))
    )
    (net (code "62") (name "5R") (class "Default")
      (node (ref "C10") (pin "1") (pinfunction "1_1") (pintype "passive"))
      (node (ref "C11") (pin "2") (pinfunction "2_2") (pintype "passive"))
      (node (ref "C4") (pin "1") (pinfunction "1_1") (pintype "passive"))
      (node (ref "C7") (pin "2") (pinfunction "2_2") (pintype "passive"))
      (node (ref "D2") (pin "2") (pinfunction "K_2") (pintype "passive"))
      (node (ref "J14") (pin "1") (pinfunction "1_1") (pintype "passive"))
      (node (ref "J15") (pin "1") (pinfunction "1_1") (pintype "passive"))
      (node (ref "U1") (pin "2") (pinfunction "O_2") (pintype "passive"))
      (node (ref "U2") (pin "1") (pinfunction "VIN_1") (pintype "passive"))
      (node (ref "U2") (pin "3") (pinfunction "CE_3") (pintype "passive"))
      (node (ref "U3") (pin "1") (pinfunction "VOUT_1") (pintype "passive"))
    )
    (net (code "63") (name "12R2") (class "Default")
      (node (ref "D1") (pin "1") (pinfunction "A_1") (pintype "passive"))
      (node (ref "R9") (pin "2") (pinfunction "2_2") (pintype "passive"))
    )
    (net (code "64") (name "GND") (class "Default")
      (node (ref "ANT1") (pin "2") (pinfunction "GND_2") (pintype "passive"))
      (node (ref "ANT1") (pin "3") (pinfunction "GND_3") (pintype "passive"))
      (node (ref "C10") (pin "2") (pinfunction "2_2") (pintype "passive"))
      (node (ref "C11") (pin "1") (pinfunction "1_1") (pintype "passive"))
      (node (ref "C12") (pin "1") (pinfunction "1_1") (pintype "passive"))
      (node (ref "C13") (pin "1") (pinfunction "1_1") (pintype "passive"))
      (node (ref "C14") (pin "2") (pinfunction "2_2") (pintype "passive"))
      (node (ref "C15") (pin "1") (pinfunction "1_1") (pintype "passive"))
      (node (ref "C20") (pin "1") (pinfunction "1_1") (pintype "passive"))
      (node (ref "C21") (pin "1") (pinfunction "1_1") (pintype "passive"))
      (node (ref "C22") (pin "1") (pinfunction "1_1") (pintype "passive"))
      (node (ref "C23") (pin "1") (pinfunction "1_1") (pintype "passive"))
      (node (ref "C24") (pin "1") (pinfunction "1_1") (pintype "passive"))
      (node (ref "C25") (pin "1") (pinfunction "1_1") (pintype "passive"))
      (node (ref "C26") (pin "1") (pinfunction "1_1") (pintype "passive"))
      (node (ref "C27") (pin "1") (pinfunction "1_1") (pintype "passive"))
      (node (ref "C28") (pin "1") (pinfunction "1_1") (pintype "passive"))
      (node (ref "C29") (pin "1") (pinfunction "1_1") (pintype "passive"))
      (node (ref "C30") (pin "1") (pinfunction "1_1") (pintype "passive"))
      (node (ref "C31") (pin "1") (pinfunction "1_1") (pintype "passive"))
      (node (ref "C32") (pin "1") (pinfunction "1_1") (pintype "passive"))
      (node (ref "C33") (pin "1") (pinfunction "1_1") (pintype "passive"))
      (node (ref "C34") (pin "1") (pinfunction "1_1") (pintype "passive"))
      (node (ref "C35") (pin "1") (pinfunction "1_1") (pintype "passive"))
      (node (ref "C36") (pin "1") (pinfunction "1_1") (pintype "passive"))
      (node (ref "C4") (pin "2") (pinfunction "2_2") (pintype "passive"))
      (node (ref "C40") (pin "1") (pinfunction "1_1") (pintype "passive"))
      (node (ref "C41") (pin "1") (pinfunction "1_1") (pintype "passive"))
      (node (ref "C42") (pin "1") (pinfunction "1_1") (pintype "passive"))
      (node (ref "C43") (pin "1") (pinfunction "1_1") (pintype "passive"))
      (node (ref "C44") (pin "1") (pinfunction "1_1") (pintype "passive"))
      (node (ref "C46") (pin "1") (pinfunction "1_1") (pintype "passive"))
      (node (ref "C7") (pin "1") (pinfunction "1_1") (pintype "passive"))
      (node (ref "J10") (pin "5") (pinfunction "FGND1_5") (pintype "passive"))
      (node (ref "J11") (pin "4") (pinfunction "4_4") (pintype "passive"))
      (node (ref "J12") (pin "4") (pinfunction "4_4") (pintype "passive"))
      (node (ref "J13") (pin "4") (pinfunction "4_4") (pintype "passive"))
      (node (ref "J14") (pin "12") (pinfunction "12_12") (pintype "passive"))
      (node (ref "J15") (pin "12") (pinfunction "12_12") (pintype "passive"))
      (node (ref "L3") (pin "1") (pinfunction "1_1") (pintype "passive"))
      (node (ref "L4") (pin "1") (pinfunction "1_1") (pintype "passive"))
      (node (ref "LD1") (pin "2") (pinfunction "K_2") (pintype "passive"))
      (node (ref "R22") (pin "1") (pinfunction "1_1") (pintype "passive"))
      (node (ref "R3") (pin "1") (pinfunction "1_1") (pintype "passive"))
      (node (ref "R30") (pin "1") (pinfunction "1_1") (pintype "passive"))
      (node (ref "R32") (pin "1") (pinfunction "1_1") (pintype "passive"))
      (node (ref "R34") (pin "1") (pinfunction "1_1") (pintype "passive"))
      (node (ref "R36") (pin "1") (pinfunction "1_1") (pintype "passive"))
      (node (ref "R38") (pin "1") (pinfunction "1_1") (pintype "passive"))
      (node (ref "R4") (pin "1") (pinfunction "1_1") (pintype "passive"))
      (node (ref "R40") (pin "1") (pinfunction "1_1") (pintype "passive"))
      (node (ref "R6") (pin "1") (pinfunction "1_1") (pintype "passive"))
      (node (ref "SW2") (pin "1") (pintype "passive"))
      (node (ref "U10") (pin "3") (pinfunction "GND_3") (pintype "passive"))
      (node (ref "U10") (pin "4") (pinfunction "CSB_4") (pintype "passive"))
      (node (ref "U10") (pin "5") (pinfunction "CSB_5") (pintype "passive"))
      (node (ref "U11") (pin "12") (pinfunction "GND_12") (pintype "passive"))
      (node (ref "U12") (pin "1") (pinfunction "CLKIN_1") (pintype "passive"))
      (node (ref "U12") (pin "18") (pinfunction "GND_18") (pintype "passive"))
      (node (ref "U13") (pin "11") (pinfunction "GND_11") (pintype "passive"))
      (node (ref "U13") (pin "9") (pinfunction "GND_9") (pintype "passive"))
      (node (ref "U14") (pin "14") (pinfunction "GND_14") (pintype "passive"))
      (node (ref "U14") (pin "17") (pinfunction "GND_17") (pintype "passive"))
      (node (ref "U14") (pin "20") (pinfunction "GND_20") (pintype "passive"))
      (node (ref "U14") (pin "8") (pinfunction "GND_8") (pintype "passive"))
      (node (ref "U2") (pin "2") (pinfunction "VSS_2") (pintype "passive"))
      (node (ref "U4") (pin "12") (pinfunction "VSSA_12") (pintype "power_in"))
      (node (ref "U4") (pin "18") (pinfunction "VSS_4_18") (pintype "power_in"))
      (node (ref "U4") (pin "31") (pinfunction "VSS_1_31") (pintype "power_in"))
      (node (ref "U4") (pin "47") (pinfunction "VSS_2_47") (pintype "power_in"))
      (node (ref "U4") (pin "63") (pinfunction "VSS_3_63") (pintype "power_in"))
      (node (ref "U5") (pin "4") (pinfunction "V-_4") (pintype "power_in"))
    )
    (net (code "65") (name "Net-(ANT1-SIG)") (class "Default")
      (node (ref "ANT1") (pin "1") (pinfunction "SIG_1") (pintype "passive"))
      (node (ref "C45") (pin "1") (pinfunction "1_1") (pintype "passive"))
      (node (ref "C46") (pin "2") (pinfunction "2_2") (pintype "passive"))
    )
    (net (code "66") (name "Net-(C42-Pad2)") (class "Default")
      (node (ref "C42") (pin "2") (pinfunction "2_2") (pintype "passive"))
      (node (ref "U14") (pin "19") (pinfunction "VDD_19") (pintype "passive"))
    )
    (net (code "67") (name "Net-(C45-Pad2)") (class "Default")
      (node (ref "C45") (pin "2") (pinfunction "2_2") (pintype "passive"))
      (node (ref "L10") (pin "2") (pinfunction "2_2") (pintype "passive"))
    )
    (net (code "68") (name "Net-(D1-K)") (class "Default")
      (node (ref "C1") (pin "1") (pinfunction "1_1") (pintype "passive"))
      (node (ref "D1") (pin "2") (pinfunction "K_2") (pintype "passive"))
      (node (ref "L1") (pin "1") (pinfunction "1_1") (pintype "passive"))
    )
    (net (code "69") (name "Net-(D2-A)") (class "Default")
      (node (ref "D2") (pin "1") (pinfunction "A_1") (pintype "passive"))
      (node (ref "L5") (pin "1") (pinfunction "1_1") (pintype "passive"))
    )
    (net (code "70") (name "Net-(D10-A)") (class "Default")
      (node (ref "D10") (pin "1") (pinfunction "A_1") (pintype "passive"))
      (node (ref "M1") (pin "2") (pinfunction "2_2") (pintype "passive"))
      (node (ref "Q2") (pin "3") (pinfunction "D_3") (pintype "passive"))
    )
    (net (code "71") (name "Net-(D11-A)") (class "Default")
      (node (ref "D11") (pin "1") (pinfunction "A_1") (pintype "passive"))
      (node (ref "M2") (pin "2") (pinfunction "2_2") (pintype "passive"))
      (node (ref "Q3") (pin "3") (pinfunction "D_3") (pintype "passive"))
    )
    (net (code "72") (name "Net-(D12-A)") (class "Default")
      (node (ref "D12") (pin "1") (pinfunction "A_1") (pintype "passive"))
      (node (ref "M3") (pin "2") (pinfunction "2_2") (pintype "passive"))
      (node (ref "Q4") (pin "3") (pinfunction "D_3") (pintype "passive"))
    )
    (net (code "73") (name "Net-(D13-A)") (class "Default")
      (node (ref "D13") (pin "1") (pinfunction "A_1") (pintype "passive"))
      (node (ref "M4") (pin "2") (pinfunction "2_2") (pintype "passive"))
      (node (ref "Q5") (pin "3") (pinfunction "D_3") (pintype "passive"))
    )
    (net (code "74") (name "Net-(D14-A)") (class "Default")
      (node (ref "D14") (pin "1") (pinfunction "A_1") (pintype "passive"))
      (node (ref "M5") (pin "2") (pinfunction "2_2") (pintype "passive"))
      (node (ref "Q6") (pin "3") (pinfunction "D_3") (pintype "passive"))
    )
    (net (code "75") (name "Net-(D15-A)") (class "Default")
      (node (ref "D15") (pin "1") (pinfunction "A_1") (pintype "passive"))
      (node (ref "M6") (pin "2") (pinfunction "2_2") (pintype "passive"))
      (node (ref "Q7") (pin "3") (pinfunction "D_3") (pintype "passive"))
    )
    (net (code "76") (name "Net-(J10-D+)") (class "Default")
      (node (ref "J10") (pin "2") (pinfunction "D+_2") (pintype "passive"))
      (node (ref "R11") (pin "2") (pinfunction "2_2") (pintype "passive"))
      (node (ref "R12") (pin "2") (pinfunction "2_2") (pintype "passive"))
    )
    (net (code "77") (name "Net-(J10-D-)") (class "Default")
      (node (ref "J10") (pin "3") (pinfunction "D-_3") (pintype "passive"))
      (node (ref "R13") (pin "2") (pinfunction "2_2") (pintype "passive"))
    )
    (net (code "78") (name "Net-(J10-VCC)") (class "Default")
      (node (ref "J10") (pin "1") (pinfunction "VCC_1") (pintype "passive"))
      (node (ref "L5") (pin "2") (pinfunction "2_2") (pintype "passive"))
    )
    (net (code "79") (name "Net-(J12-Pad2)") (class "Default")
      (node (ref "J12") (pin "2") (pinfunction "2_2") (pintype "passive"))
      (node (ref "R16") (pin "2") (pinfunction "2_2") (pintype "passive"))
    )
    (net (code "80") (name "Net-(J12-Pad3)") (class "Default")
      (node (ref "J12") (pin "3") (pinfunction "3_3") (pintype "passive"))
      (node (ref "R17") (pin "2") (pinfunction "2_2") (pintype "passive"))
    )
    (net (code "81") (name "Net-(J13-Pad2)") (class "Default")
      (node (ref "J13") (pin "2") (pinfunction "2_2") (pintype "passive"))
      (node (ref "R18") (pin "2") (pinfunction "2_2") (pintype "passive"))
    )
    (net (code "82") (name "Net-(J13-Pad3)") (class "Default")
      (node (ref "J13") (pin "3") (pinfunction "3_3") (pintype "passive"))
      (node (ref "R19") (pin "2") (pinfunction "2_2") (pintype "passive"))
    )
    (net (code "83") (name "Net-(LD1-A)") (class "Default")
      (node (ref "LD1") (pin "1") (pinfunction "A_1") (pintype "passive"))
      (node (ref "R1") (pin "1") (pinfunction "1_1") (pintype "passive"))
    )
    (net (code "84") (name "Net-(LD2-A)") (class "Default")
      (node (ref "LD2") (pin "1") (pinfunction "A_1") (pintype "passive"))
      (node (ref "R20") (pin "2") (pinfunction "2_2") (pintype "passive"))
    )
    (net (code "85") (name "Net-(Q1-D)") (class "Default")
      (node (ref "Q1") (pin "2") (pinfunction "D_2") (pintype "passive"))
      (node (ref "R11") (pin "1") (pinfunction "1_1") (pintype "passive"))
    )
    (net (code "86") (name "Net-(Q2-G)") (class "Default")
      (node (ref "Q2") (pin "1") (pinfunction "G_1") (pintype "passive"))
      (node (ref "R31") (pin "1") (pinfunction "1_1") (pintype "passive"))
    )
    (net (code "87") (name "Net-(Q3-G)") (class "Default")
      (node (ref "Q3") (pin "1") (pinfunction "G_1") (pintype "passive"))
      (node (ref "R33") (pin "1") (pinfunction "1_1") (pintype "passive"))
    )
    (net (code "88") (name "Net-(Q4-G)") (class "Default")
      (node (ref "Q4") (pin "1") (pinfunction "G_1") (pintype "passive"))
      (node (ref "R35") (pin "1") (pinfunction "1_1") (pintype "passive"))
    )
    (net (code "89") (name "Net-(Q5-G)") (class "Default")
      (node (ref "Q5") (pin "1") (pinfunction "G_1") (pintype "passive"))
      (node (ref "R37") (pin "1") (pinfunction "1_1") (pintype "passive"))
    )
    (net (code "90") (name "Net-(Q6-G)") (class "Default")
      (node (ref "Q6") (pin "1") (pinfunction "G_1") (pintype "passive"))
      (node (ref "R39") (pin "1") (pinfunction "1_1") (pintype "passive"))
    )
    (net (code "91") (name "Net-(Q7-G)") (class "Default")
      (node (ref "Q7") (pin "1") (pinfunction "G_1") (pintype "passive"))
      (node (ref "R41") (pin "1") (pinfunction "1_1") (pintype "passive"))
    )
    (net (code "92") (name "Net-(U1-IN)") (class "Default")
      (node (ref "C2") (pin "1") (pinfunction "1_1") (pintype "passive"))
      (node (ref "C3") (pin "2") (pinfunction "2_2") (pintype "passive"))
      (node (ref "L1") (pin "2") (pinfunction "2_2") (pintype "passive"))
      (node (ref "U1") (pin "3") (pinfunction "IN_3") (pintype "passive"))
    )
    (net (code "93") (name "Net-(U3-C+)") (class "Default")
      (node (ref "C6") (pin "2") (pinfunction "2_2") (pintype "passive"))
      (node (ref "U3") (pin "6") (pinfunction "C+_6") (pintype "passive"))
    )
    (net (code "94") (name "Net-(U3-C-)") (class "Default")
      (node (ref "C6") (pin "1") (pinfunction "1_1") (pintype "passive"))
      (node (ref "U3") (pin "4") (pinfunction "C-_4") (pintype "passive"))
    )
    (net (code "95") (name "Net-(U5A-IN+)") (class "Default")
      (node (ref "R7") (pin "1") (pinfunction "1_1") (pintype "passive"))
      (node (ref "R8") (pin "2") (pinfunction "2_2") (pintype "passive"))
      (node (ref "U5") (pin "3") (pinfunction "IN+_3") (pintype "input"))
    )
    (net (code "96") (name "Net-(U5B-IN+)") (class "Default")
      (node (ref "R10") (pin "2") (pinfunction "2_2") (pintype "passive"))
      (node (ref "R9") (pin "1") (pinfunction "1_1") (pintype "passive"))
      (node (ref "U5") (pin "5") (pinfunction "IN+_5") (pintype "input"))
    )
    (net (code "97") (name "Net-(U10-PS)") (class "Default")
      (node (ref "R21") (pin "1") (pinfunction "1_1") (pintype "passive"))
      (node (ref "U10") (pin "2") (pinfunction "PS_2") (pintype "passive"))
    )
    (net (code "98") (name "Net-(U12-CPOUT)") (class "Default")
      (node (ref "C32") (pin "2") (pinfunction "2_2") (pintype "passive"))
      (node (ref "U12") (pin "20") (pinfunction "CPOUT_20") (pintype "passive"))
    )
    (net (code "99") (name "Net-(U12-REGOUT)") (class "Default")
      (node (ref "C33") (pin "2") (pinfunction "2_2") (pintype "passive"))
      (node (ref "U12") (pin "10") (pinfunction "REGOUT_10") (pintype "passive"))
    )
    (net (code "100") (name "Net-(U13-C1)") (class "Default")
      (node (ref "C35") (pin "2") (pinfunction "2_2") (pintype "passive"))
      (node (ref "U13") (pin "10") (pinfunction "C1_10") (pintype "passive"))
    )
    (net (code "101") (name "Net-(U13-SETC)") (class "Default")
      (node (ref "C37") (pin "1") (pinfunction "1_1") (pintype "passive"))
      (node (ref "U13") (pin "12") (pinfunction "SETC_12") (pintype "passive"))
    )
    (net (code "102") (name "Net-(U13-SETP)") (class "Default")
      (node (ref "C37") (pin "2") (pinfunction "2_2") (pintype "passive"))
      (node (ref "U13") (pin "8") (pinfunction "SETP_8") (pintype "passive"))
    )
    (net (code "103") (name "Net-(U14-ANT1)") (class "Default")
      (node (ref "L11") (pin "1") (pinfunction "1_1") (pintype "passive"))
      (node (ref "L12") (pin "1") (pinfunction "1_1") (pintype "passive"))
      (node (ref "U14") (pin "12") (pinfunction "ANT1_12") (pintype "passive"))
    )
    (net (code "104") (name "Net-(U14-ANT2)") (class "Default")
      (node (ref "L10") (pin "1") (pinfunction "1_1") (pintype "passive"))
      (node (ref "L12") (pin "2") (pinfunction "2_2") (pintype "passive"))
      (node (ref "U14") (pin "13") (pinfunction "ANT2_13") (pintype "passive"))
    )
    (net (code "105") (name "Net-(U14-IREF)") (class "Default")
      (node (ref "R22") (pin "2") (pinfunction "2_2") (pintype "passive"))
      (node (ref "U14") (pin "16") (pinfunction "IREF_16") (pintype "passive"))
    )
    (net (code "106") (name "Net-(U14-VDD_PA)") (class "Default")
      (node (ref "L11") (pin "2") (pinfunction "2_2") (pintype "passive"))
      (node (ref "U14") (pin "11") (pinfunction "VDD_PA_11") (pintype "passive"))
    )
    (net (code "107") (name "Net-(U14-XC1)") (class "Default")
      (node (ref "C43") (pin "2") (pinfunction "2_2") (pintype "passive"))
      (node (ref "R23") (pin "1") (pinfunction "1_1") (pintype "passive"))
      (node (ref "U14") (pin "10") (pinfunction "XC1_10") (pintype "passive"))
      (node (ref "X2") (pin "3") (pintype "passive"))
    )
    (net (code "108") (name "Net-(U14-XC2)") (class "Default")
      (node (ref "C44") (pin "2") (pinfunction "2_2") (pintype "passive"))
      (node (ref "R23") (pin "2") (pinfunction "2_2") (pintype "passive"))
      (node (ref "U14") (pin "9") (pinfunction "XC2_9") (pintype "passive"))
      (node (ref "X2") (pin "1") (pintype "passive"))
    )
    (net (code "109") (name "unconnected-(C36-Pad2)") (class "Default")
      (node (ref "C36") (pin "2") (pinfunction "2_2") (pintype "passive"))
    )
    (net (code "110") (name "unconnected-(J10-G-Pad4)") (class "Default")
      (node (ref "J10") (pin "4") (pinfunction "G_4") (pintype "passive+no_connect"))
    )
    (net (code "111") (name "unconnected-(U2-NC-Pad4)") (class "Default")
      (node (ref "U2") (pin "4") (pinfunction "NC_4") (pintype "passive+no_connect"))
    )
    (net (code "112") (name "unconnected-(U10-SDO-Pad6)") (class "Default")
      (node (ref "U10") (pin "6") (pinfunction "SDO_6") (pintype "passive+no_connect"))
    )
    (net (code "113") (name "unconnected-(U11-NC-Pad5)") (class "Default")
      (node (ref "U11") (pin "5") (pinfunction "NC_5") (pintype "passive+no_connect"))
    )
    (net (code "114") (name "unconnected-(U11-NC-Pad6)") (class "Default")
      (node (ref "U11") (pin "6") (pinfunction "NC_6") (pintype "passive"))
    )
    (net (code "115") (name "unconnected-(U11-NC-Pad7)") (class "Default")
      (node (ref "U11") (pin "7") (pinfunction "NC_7") (pintype "passive+no_connect"))
    )
    (net (code "116") (name "unconnected-(U11-NC-Pad8)") (class "Default")
      (node (ref "U11") (pin "8") (pinfunction "NC_8") (pintype "passive+no_connect"))
    )
    (net (code "117") (name "unconnected-(U11-NC-Pad10)") (class "Default")
      (node (ref "U11") (pin "10") (pinfunction "NC_10") (pintype "passive+no_connect"))
    )
    (net (code "118") (name "unconnected-(U11-PIO0-Pad16)") (class "Default")
      (node (ref "U11") (pin "16") (pinfunction "PIO0_16") (pintype "passive+no_connect"))
    )
    (net (code "119") (name "unconnected-(U11-PIO2-Pad14)") (class "Default")
      (node (ref "U11") (pin "14") (pinfunction "PIO2_14") (pintype "passive+no_connect"))
    )
    (net (code "120") (name "unconnected-(U11-PIO3-Pad13)") (class "Default")
      (node (ref "U11") (pin "13") (pinfunction "PIO3_13") (pintype "passive+no_connect"))
    )
    (net (code "121") (name "unconnected-(U11-RESETB-Pad11)") (class "Default")
      (node (ref "U11") (pin "11") (pinfunction "RESETB_11") (pintype "passive+no_connect"))
    )
    (net (code "122") (name "unconnected-(U11-UART_CTS-Pad3)") (class "Default")
      (node (ref "U11") (pin "3") (pinfunction "UART_CTS_3") (pintype "passive+no_connect"))
    )
    (net (code "123") (name "unconnected-(U11-UART_RTS-Pad1)") (class "Default")
      (node (ref "U11") (pin "1") (pinfunction "UART_RTS_1") (pintype "passive"))
    )
    (net (code "124") (name "unconnected-(U12-CLKOUT-Pad22)") (class "Default")
      (node (ref "U12") (pin "22") (pinfunction "CLKOUT_22") (pintype "passive+no_connect"))
    )
    (net (code "125") (name "unconnected-(U12-FSYNC-Pad11)") (class "Default")
      (node (ref "U12") (pin "11") (pinfunction "FSYNC_11") (pintype "passive+no_connect"))
    )
    (net (code "126") (name "unconnected-(U12-RESV-Pad19)") (class "Default")
      (node (ref "U12") (pin "19") (pinfunction "RESV_19") (pintype "passive+no_connect"))
    )
    (net (code "127") (name "unconnected-(U12-RESV-Pad21)") (class "Default")
      (node (ref "U12") (pin "21") (pinfunction "RESV_21") (pintype "passive+no_connect"))
    )
    (net (code "128") (name "unconnected-(U13-DRDY-Pad15)") (class "Default")
      (node (ref "U13") (pin "15") (pinfunction "DRDY_15") (pintype "passive+no_connect"))
    )
    (net (code "129") (name "unconnected-(U13-NC-Pad3)") (class "Default")
      (node (ref "U13") (pin "3") (pinfunction "NC_3") (pintype "passive+no_connect"))
    )
    (net (code "130") (name "unconnected-(U13-NC-Pad5)") (class "Default")
      (node (ref "U13") (pin "5") (pinfunction "NC_5") (pintype "passive+no_connect"))
    )
    (net (code "131") (name "unconnected-(U13-NC-Pad7)") (class "Default")
      (node (ref "U13") (pin "7") (pinfunction "NC_7") (pintype "passive+no_connect"))
    )
    (net (code "132") (name "unconnected-(U13-NC-Pad14)") (class "Default")
      (node (ref "U13") (pin "14") (pinfunction "NC_14") (pintype "passive+no_connect"))
    )
    (net (code "133") (name "unconnected-(X1-Pad2)") (class "Default")
      (node (ref "X1") (pin "2") (pintype "passive+no_connect"))
    )
    (net (code "134") (name "unconnected-(X1-Pad4)") (class "Default")
      (node (ref "X1") (pin "4") (pintype "passive+no_connect"))
    )
    (net (code "135") (name "unconnected-(X2-Pad2)") (class "Default")
      (node (ref "X2") (pin "2") (pintype "passive+no_connect"))
    )
    (net (code "136") (name "unconnected-(X2-Pad4)") (class "Default")
      (node (ref "X2") (pin "4") (pintype "passive+no_connect"))
    )
  )
)
